# OBD-II-UART.net
KiCad netlist of a schematic drawn in EAGLE
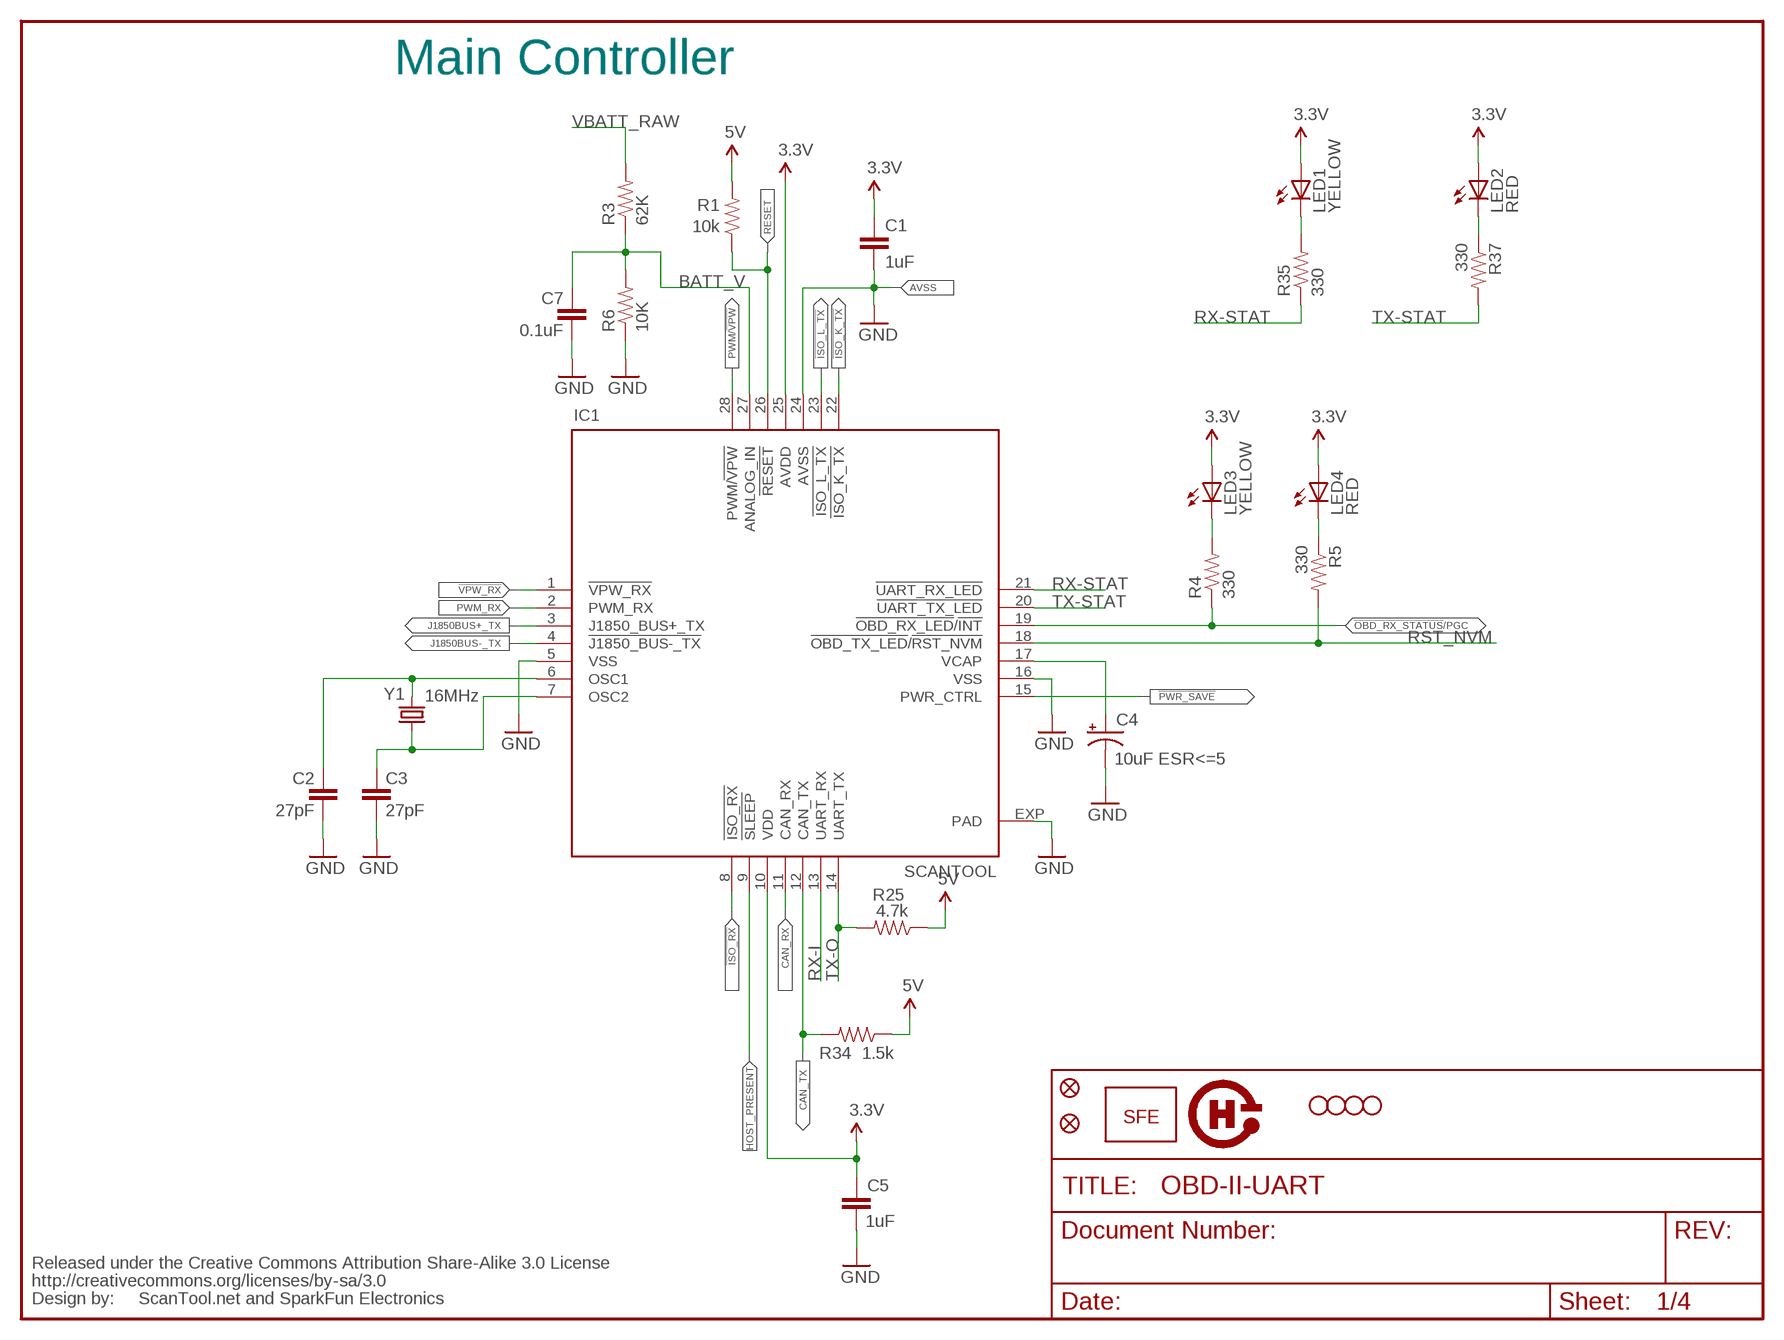
[diagram p0: schematic, sheet 1]
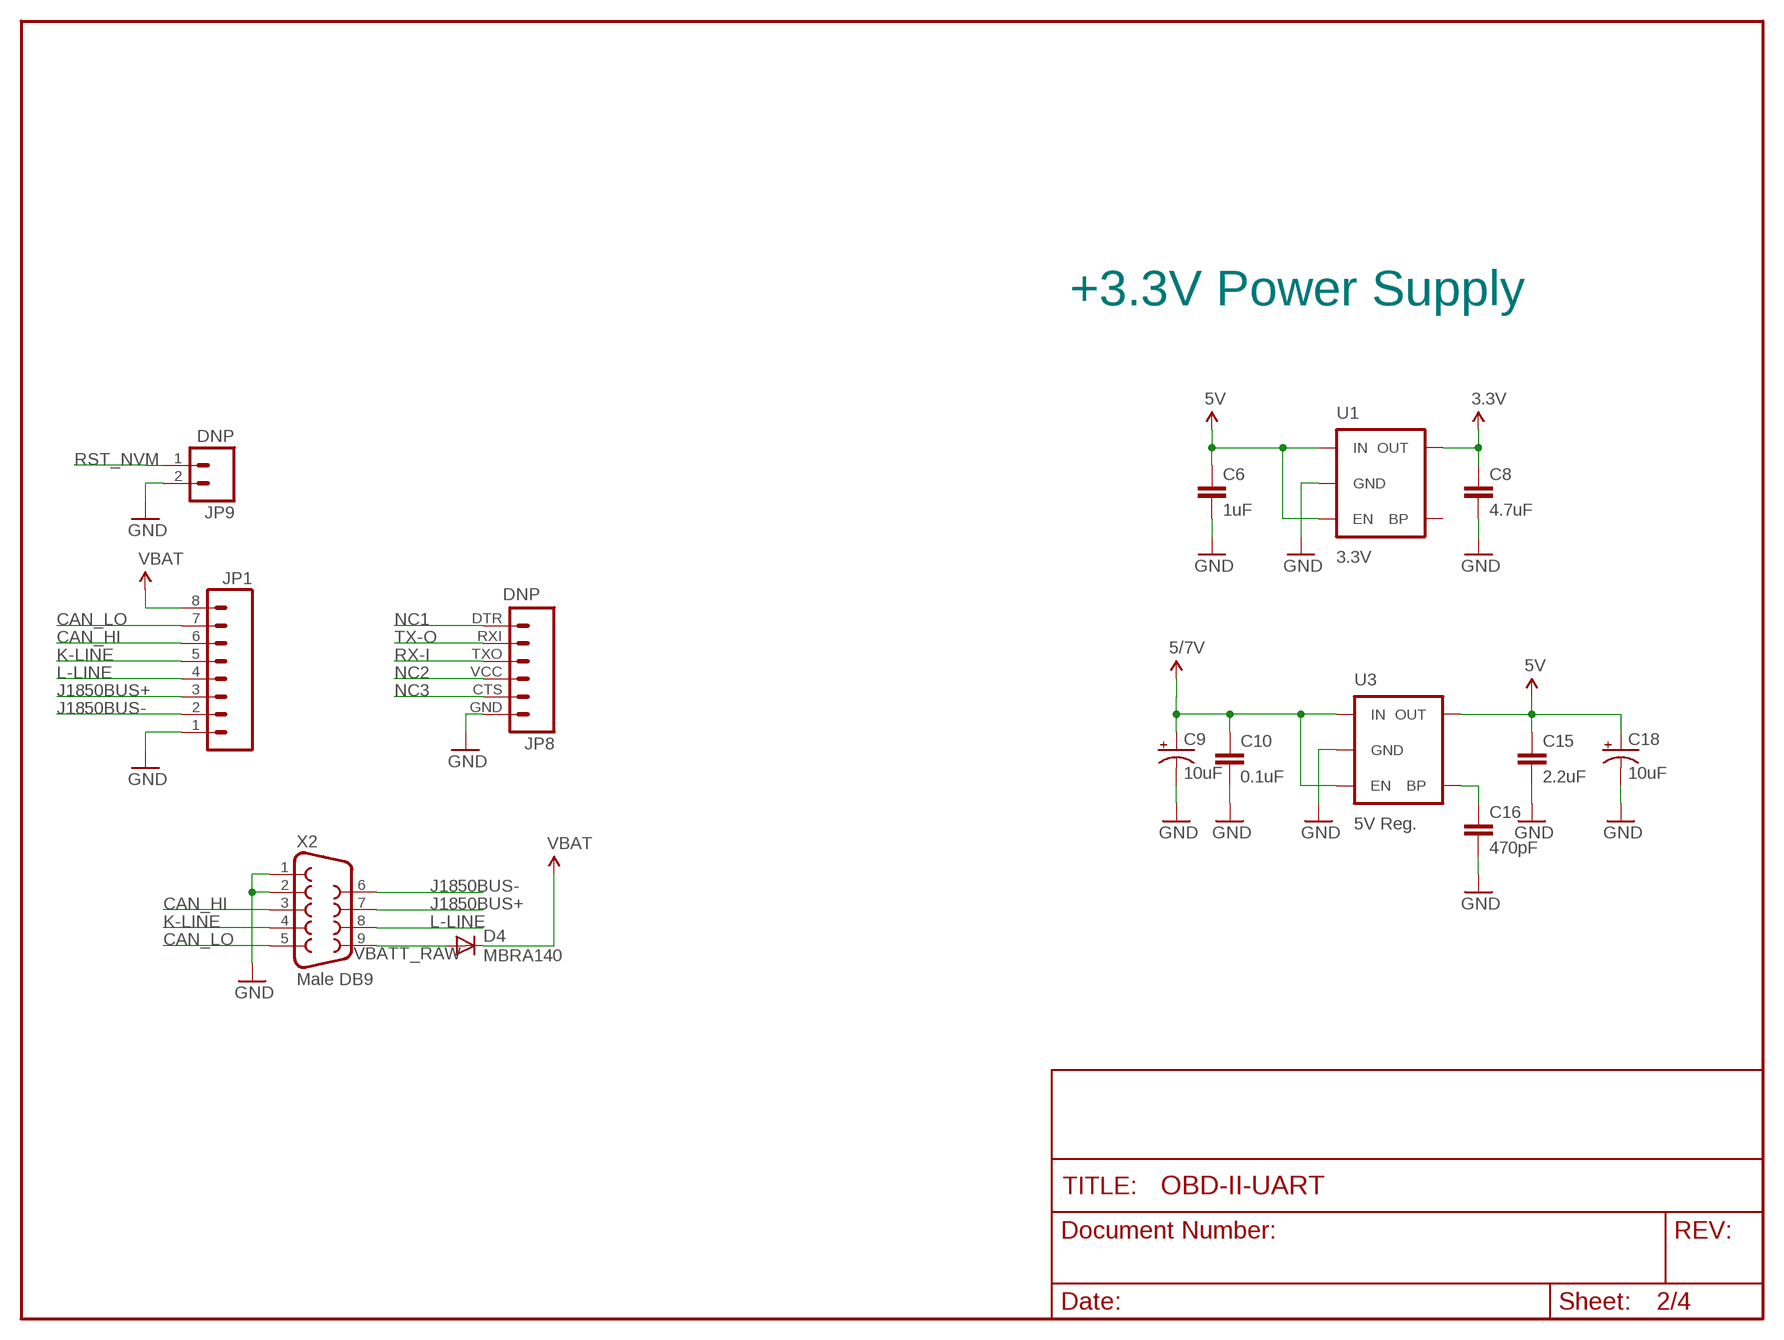
[diagram p1: schematic, sheet 2]
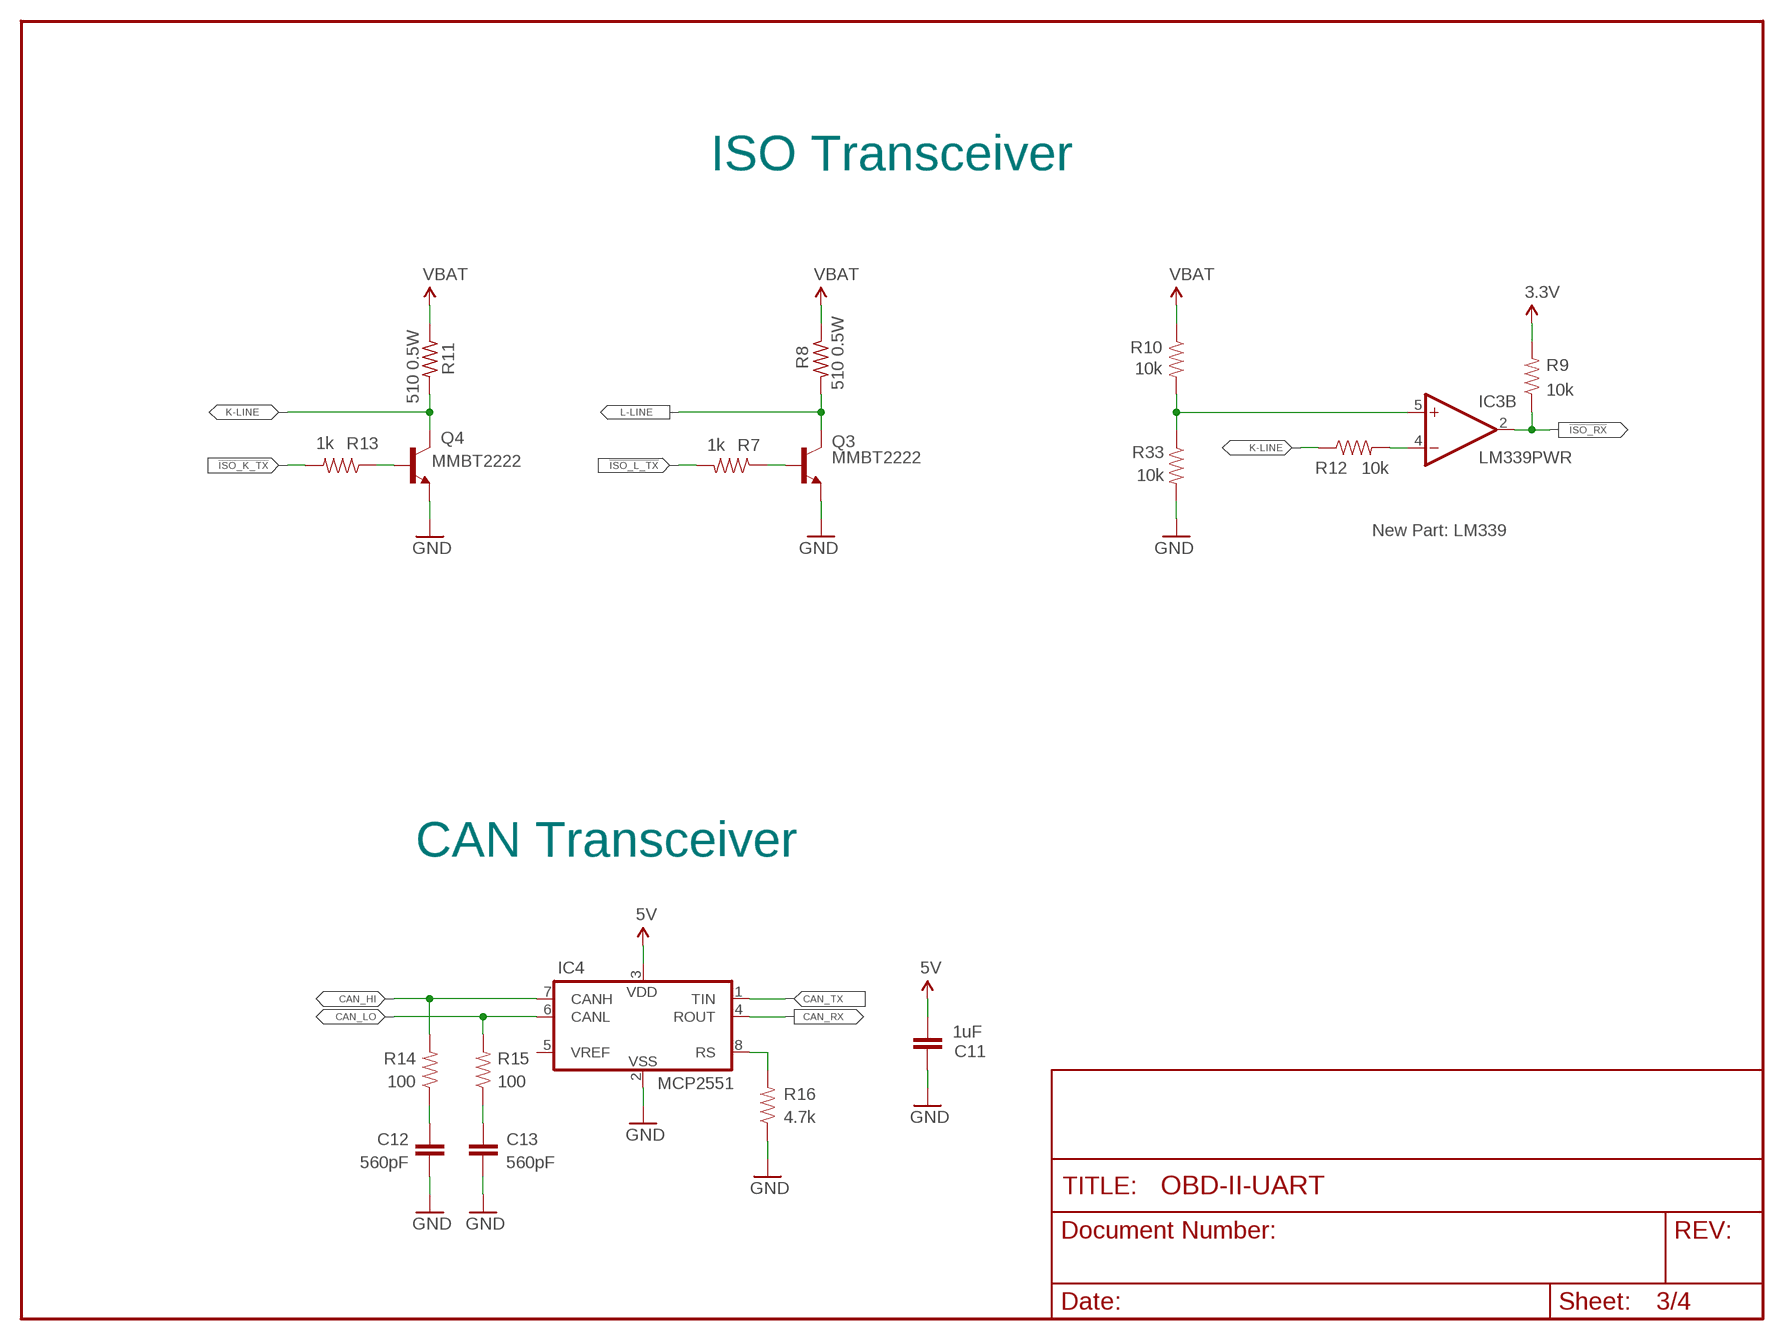
[diagram p2: schematic, sheet 3]
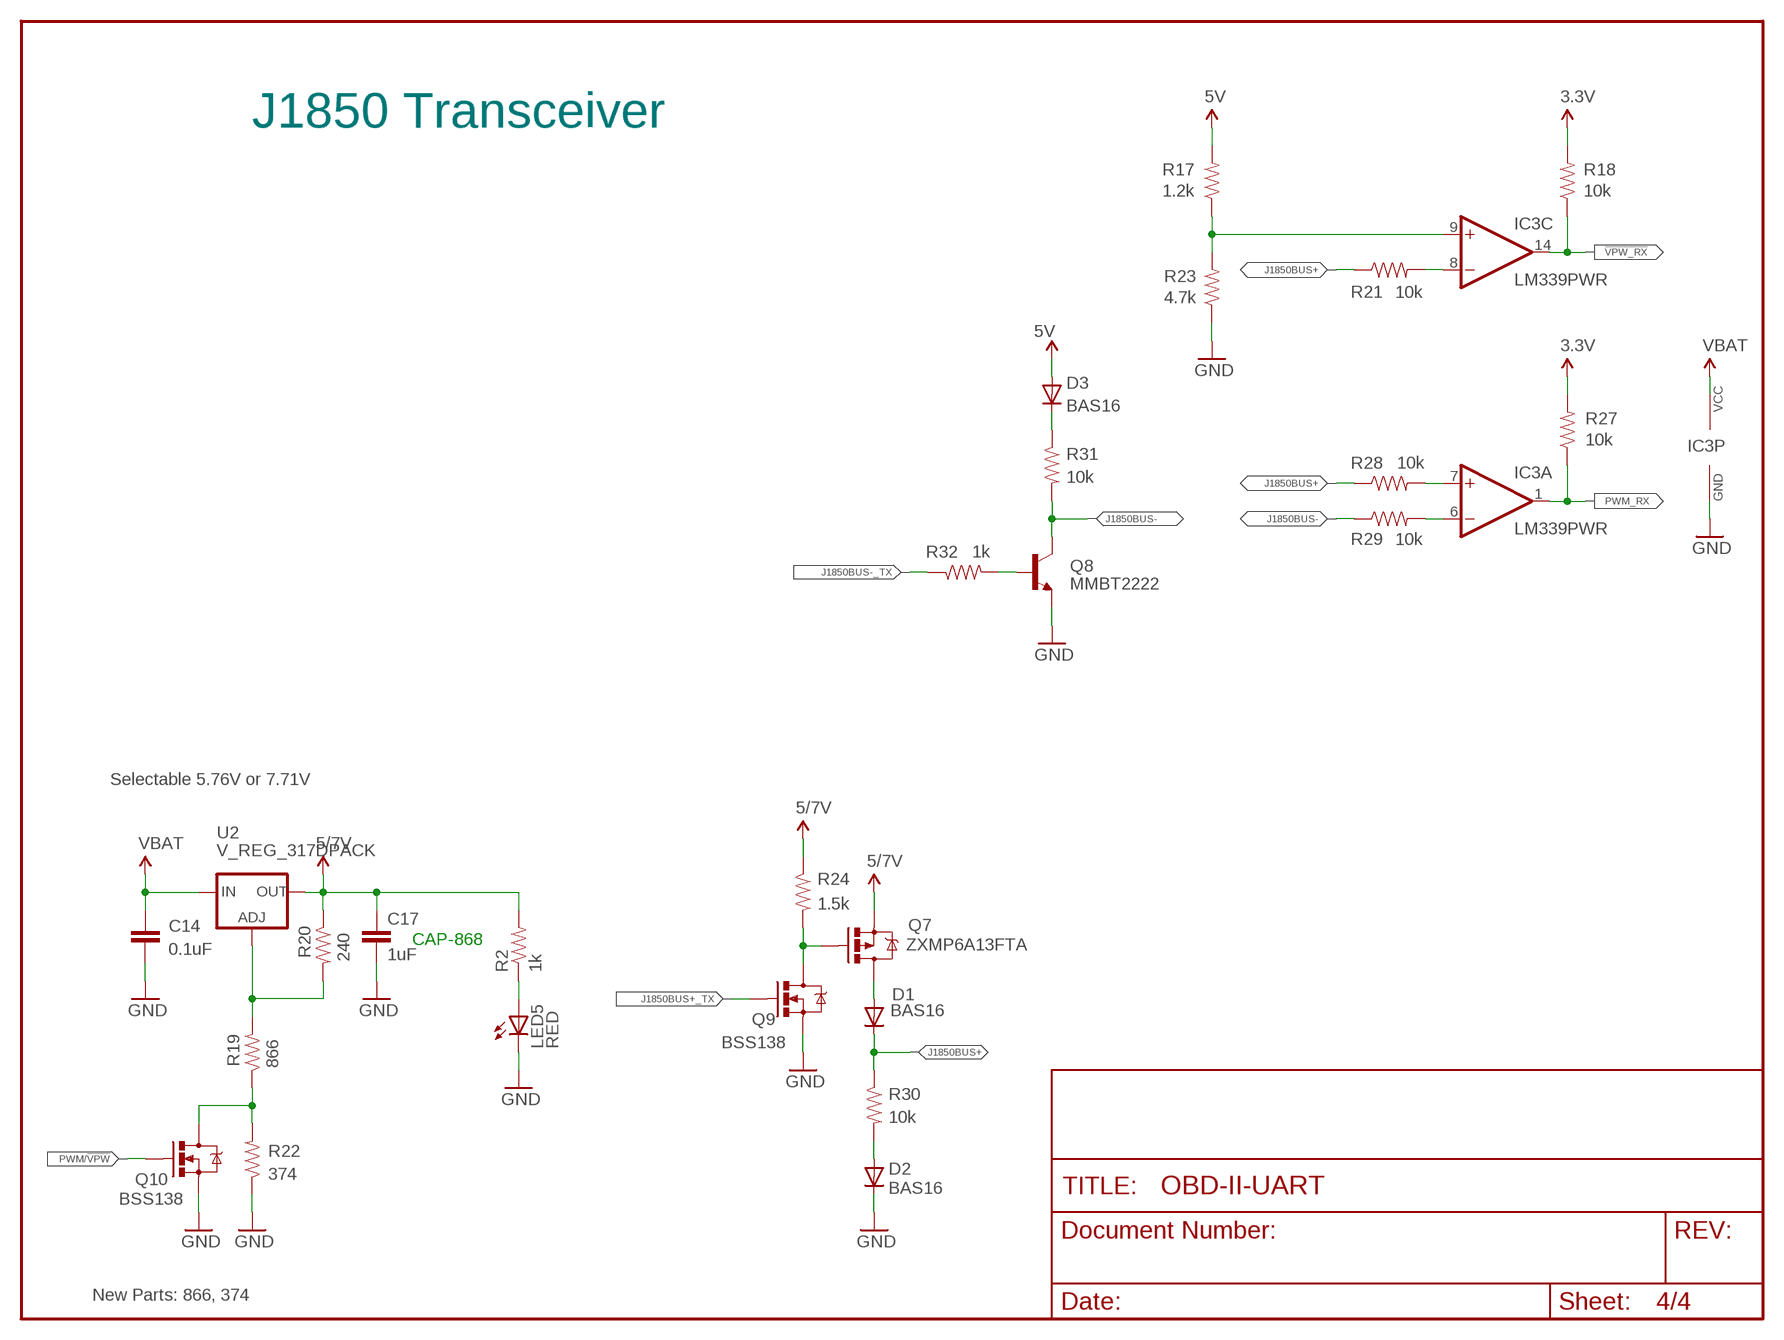
[diagram p3: schematic, sheet 4]

(export (version "E")
  (design (tool "Eeschema 10.0.6"))
  (components
    (comp (ref "C14")
      (value "0.1uF")
      (footprint "eagle-import:0402-CAP")
      (libsource (lib "eagle-import") (part "CAP0402-CAP"))
    )
    (comp (ref "C17")
      (value "1uF")
      (footprint "eagle-import:0402-CAP")
      (libsource (lib "eagle-import") (part "CAP0402-CAP"))
    )
    (comp (ref "D1")
      (value "BAS16")
      (footprint "eagle-import:SOD-323")
      (libsource (lib "eagle-import") (part "DIODESOD"))
    )
    (comp (ref "D2")
      (value "BAS16")
      (footprint "eagle-import:SOD-323")
      (libsource (lib "eagle-import") (part "DIODESOD"))
    )
    (comp (ref "D3")
      (value "BAS16")
      (footprint "eagle-import:SOD-323")
      (libsource (lib "eagle-import") (part "DIODESOD"))
    )
    (comp (ref "IC3")
      (value "LM339PWR")
      (footprint "eagle-import:TSSOP-14")
      (libsource (lib "eagle-import") (part "LM339PWR"))
    )
    (comp (ref "LED5")
      (value "RED")
      (footprint "eagle-import:LED-0603")
      (libsource (lib "eagle-import") (part "LED0603"))
    )
    (comp (ref "Q7")
      (value "ZXMP6A13FTA")
      (footprint "eagle-import:SOT23")
      (libsource (lib "eagle-import") (part "MOSFET-PCHANNEL"))
    )
    (comp (ref "Q8")
      (value "MMBT2222")
      (footprint "eagle-import:SOT23-3")
      (libsource (lib "eagle-import") (part "TRANSISTOR_NPNSOT23-3"))
    )
    (comp (ref "Q9")
      (value "BSS138")
      (footprint "eagle-import:SOT23-3")
      (libsource (lib "eagle-import") (part "MOSFET-NCHANNELSMD"))
    )
    (comp (ref "Q10")
      (value "BSS138")
      (footprint "eagle-import:SOT23-3")
      (libsource (lib "eagle-import") (part "MOSFET-NCHANNELSMD"))
    )
    (comp (ref "R2")
      (value "1k")
      (footprint "eagle-import:0402-RES")
      (libsource (lib "eagle-import") (part "RESISTOR0402-RES"))
    )
    (comp (ref "R17")
      (value "1.2k")
      (footprint "eagle-import:0402-RES")
      (libsource (lib "eagle-import") (part "RESISTOR0402-RES"))
    )
    (comp (ref "R18")
      (value "10k")
      (footprint "eagle-import:0402-RES")
      (libsource (lib "eagle-import") (part "RESISTOR0402-RES"))
    )
    (comp (ref "R19")
      (value "866")
      (footprint "eagle-import:0402-RES")
      (libsource (lib "eagle-import") (part "RESISTOR0402-RES"))
    )
    (comp (ref "R20")
      (value "240")
      (footprint "eagle-import:0402-RES")
      (libsource (lib "eagle-import") (part "RESISTOR0402-RES"))
    )
    (comp (ref "R21")
      (value "10k")
      (footprint "eagle-import:0402-RES")
      (libsource (lib "eagle-import") (part "RESISTOR0402-RES"))
    )
    (comp (ref "R22")
      (value "374")
      (footprint "eagle-import:0402-RES")
      (libsource (lib "eagle-import") (part "RESISTOR0402-RES"))
    )
    (comp (ref "R23")
      (value "4.7k")
      (footprint "eagle-import:0402-RES")
      (libsource (lib "eagle-import") (part "RESISTOR0402-RES"))
    )
    (comp (ref "R24")
      (value "1.5k")
      (footprint "eagle-import:0402-RES")
      (libsource (lib "eagle-import") (part "RESISTOR0402-RES"))
    )
    (comp (ref "R27")
      (value "10k")
      (footprint "eagle-import:0402-RES")
      (libsource (lib "eagle-import") (part "RESISTOR0402-RES"))
    )
    (comp (ref "R28")
      (value "10k")
      (footprint "eagle-import:0402-RES")
      (libsource (lib "eagle-import") (part "RESISTOR0402-RES"))
    )
    (comp (ref "R29")
      (value "10k")
      (footprint "eagle-import:0402-RES")
      (libsource (lib "eagle-import") (part "RESISTOR0402-RES"))
    )
    (comp (ref "R30")
      (value "10k")
      (footprint "eagle-import:0402-RES")
      (libsource (lib "eagle-import") (part "RESISTOR0402-RES"))
    )
    (comp (ref "R31")
      (value "10k")
      (footprint "eagle-import:0402-RES")
      (libsource (lib "eagle-import") (part "RESISTOR0402-RES"))
    )
    (comp (ref "R32")
      (value "1k")
      (footprint "eagle-import:0402-RES")
      (libsource (lib "eagle-import") (part "RESISTOR0402-RES"))
    )
    (comp (ref "U2")
      (value "V_REG_317DPACK")
      (footprint "eagle-import:V-REG_DPACK")
      (libsource (lib "eagle-import") (part "V_REG_317DPACK"))
    )
    (comp (ref "C11")
      (value "1uF")
      (footprint "eagle-import:0402-CAP")
      (libsource (lib "eagle-import") (part "CAP0402-CAP"))
    )
    (comp (ref "C12")
      (value "560pF")
      (footprint "eagle-import:0402-CAP")
      (libsource (lib "eagle-import") (part "CAP0402-CAP"))
    )
    (comp (ref "C13")
      (value "560pF")
      (footprint "eagle-import:0402-CAP")
      (libsource (lib "eagle-import") (part "CAP0402-CAP"))
    )
    (comp (ref "IC4")
      (value "MCP2551")
      (footprint "eagle-import:SO-8")
      (fields (field (name "PARTNUM") "MCP2551-I/SN"))
      (libsource (lib "eagle-import") (part "MCP2551-I/SN"))
    )
    (comp (ref "Q3")
      (value "MMBT2222")
      (footprint "eagle-import:SOT23-3")
      (libsource (lib "eagle-import") (part "TRANSISTOR_NPNSOT23-3"))
    )
    (comp (ref "Q4")
      (value "MMBT2222")
      (footprint "eagle-import:SOT23-3")
      (libsource (lib "eagle-import") (part "TRANSISTOR_NPNSOT23-3"))
    )
    (comp (ref "R7")
      (value "1k")
      (footprint "eagle-import:0402-RES")
      (libsource (lib "eagle-import") (part "RESISTOR0402-RES"))
    )
    (comp (ref "R8")
      (value "510 0.5W")
      (footprint "eagle-import:2010")
      (libsource (lib "eagle-import") (part "R-US_2010"))
    )
    (comp (ref "R9")
      (value "10k")
      (footprint "eagle-import:0402-RES")
      (libsource (lib "eagle-import") (part "RESISTOR0402-RES"))
    )
    (comp (ref "R10")
      (value "10k")
      (footprint "eagle-import:0402-RES")
      (libsource (lib "eagle-import") (part "RESISTOR0402-RES"))
    )
    (comp (ref "R11")
      (value "510 0.5W")
      (footprint "eagle-import:2010")
      (libsource (lib "eagle-import") (part "R-US_2010"))
    )
    (comp (ref "R12")
      (value "10k")
      (footprint "eagle-import:0402-RES")
      (libsource (lib "eagle-import") (part "RESISTOR0402-RES"))
    )
    (comp (ref "R13")
      (value "1k")
      (footprint "eagle-import:0402-RES")
      (libsource (lib "eagle-import") (part "RESISTOR0402-RES"))
    )
    (comp (ref "R14")
      (value "100")
      (footprint "eagle-import:0402-RES")
      (libsource (lib "eagle-import") (part "RESISTOR0402-RES"))
    )
    (comp (ref "R15")
      (value "100")
      (footprint "eagle-import:0402-RES")
      (libsource (lib "eagle-import") (part "RESISTOR0402-RES"))
    )
    (comp (ref "R16")
      (value "4.7k")
      (footprint "eagle-import:0402-RES")
      (libsource (lib "eagle-import") (part "RESISTOR0402-RES"))
    )
    (comp (ref "R33")
      (value "10k")
      (footprint "eagle-import:0402-RES")
      (libsource (lib "eagle-import") (part "RESISTOR0402-RES"))
    )
    (comp (ref "C1")
      (value "1uF")
      (footprint "eagle-import:0402-CAP")
      (libsource (lib "eagle-import") (part "CAP0402-CAP"))
    )
    (comp (ref "C2")
      (value "27pF")
      (footprint "eagle-import:0402-CAP")
      (libsource (lib "eagle-import") (part "CAP0402-CAP"))
    )
    (comp (ref "C3")
      (value "27pF")
      (footprint "eagle-import:0402-CAP")
      (libsource (lib "eagle-import") (part "CAP0402-CAP"))
    )
    (comp (ref "C4")
      (value "10uF ESR<=5")
      (footprint "eagle-import:EIA3216")
      (libsource (lib "eagle-import") (part "CAP_POL1206"))
    )
    (comp (ref "C5")
      (value "1uF")
      (footprint "eagle-import:0402-CAP")
      (libsource (lib "eagle-import") (part "CAP0402-CAP"))
    )
    (comp (ref "C7")
      (value "0.1uF")
      (footprint "eagle-import:0402-CAP")
      (libsource (lib "eagle-import") (part "CAP0402-CAP"))
    )
    (comp (ref "IC1")
      (value "SCANTOOL")
      (footprint "eagle-import:_STN_SCANTOOL_QFN-28-S")
      (libsource (lib "eagle-import") (part "SCANTOOL"))
    )
    (comp (ref "JP2")
      (value "FIDUCIAL1X2")
      (footprint "eagle-import:FIDUCIAL-1X2")
      (libsource (lib "eagle-import") (part "FIDUCIAL1X2"))
    )
    (comp (ref "JP3")
      (value "LOGO-SFENEW")
      (footprint "eagle-import:SFE-NEW-WEBLOGO")
      (libsource (lib "eagle-import") (part "LOGO-SFENEW"))
    )
    (comp (ref "JP4")
      (value "STAND-OFF")
      (footprint "eagle-import:STAND-OFF")
      (libsource (lib "eagle-import") (part "STAND-OFF"))
    )
    (comp (ref "JP5")
      (value "STAND-OFF")
      (footprint "eagle-import:STAND-OFF")
      (libsource (lib "eagle-import") (part "STAND-OFF"))
    )
    (comp (ref "JP6")
      (value "STAND-OFF")
      (footprint "eagle-import:STAND-OFF")
      (libsource (lib "eagle-import") (part "STAND-OFF"))
    )
    (comp (ref "JP7")
      (value "STAND-OFF")
      (footprint "eagle-import:STAND-OFF")
      (libsource (lib "eagle-import") (part "STAND-OFF"))
    )
    (comp (ref "JP10")
      (value "FIDUCIAL1X2")
      (footprint "eagle-import:FIDUCIAL-1X2")
      (libsource (lib "eagle-import") (part "FIDUCIAL1X2"))
    )
    (comp (ref "LED1")
      (value "YELLOW")
      (footprint "eagle-import:LED-0603")
      (libsource (lib "eagle-import") (part "LED0603"))
    )
    (comp (ref "LED2")
      (value "RED")
      (footprint "eagle-import:LED-0603")
      (libsource (lib "eagle-import") (part "LED0603"))
    )
    (comp (ref "LED3")
      (value "YELLOW")
      (footprint "eagle-import:LED-0603")
      (libsource (lib "eagle-import") (part "LED0603"))
    )
    (comp (ref "LED4")
      (value "RED")
      (footprint "eagle-import:LED-0603")
      (libsource (lib "eagle-import") (part "LED0603"))
    )
    (comp (ref "R1")
      (value "10k")
      (footprint "eagle-import:0402-RES")
      (libsource (lib "eagle-import") (part "RESISTOR0402-RES"))
    )
    (comp (ref "R3")
      (value "62K")
      (footprint "eagle-import:0402-RES")
      (libsource (lib "eagle-import") (part "RESISTOR0402-RES"))
    )
    (comp (ref "R4")
      (value "330")
      (footprint "eagle-import:0402-RES")
      (libsource (lib "eagle-import") (part "RESISTOR0402-RES"))
    )
    (comp (ref "R5")
      (value "330")
      (footprint "eagle-import:0402-RES")
      (libsource (lib "eagle-import") (part "RESISTOR0402-RES"))
    )
    (comp (ref "R6")
      (value "10K")
      (footprint "eagle-import:0402-RES")
      (libsource (lib "eagle-import") (part "RESISTOR0402-RES"))
    )
    (comp (ref "R25")
      (value "4.7k")
      (footprint "eagle-import:0402-RES")
      (libsource (lib "eagle-import") (part "RESISTOR0402-RES"))
    )
    (comp (ref "R34")
      (value "1.5k")
      (footprint "eagle-import:0402-RES")
      (libsource (lib "eagle-import") (part "RESISTOR0402-RES"))
    )
    (comp (ref "R35")
      (value "330")
      (footprint "eagle-import:0402-RES")
      (libsource (lib "eagle-import") (part "RESISTOR0402-RES"))
    )
    (comp (ref "R37")
      (value "330")
      (footprint "eagle-import:0402-RES")
      (libsource (lib "eagle-import") (part "RESISTOR0402-RES"))
    )
    (comp (ref "U$1")
      (value "CREATIVE_COMMONS")
      (footprint "eagle-import:CREATIVE_COMMONS")
      (libsource (lib "eagle-import") (part "CREATIVE_COMMONS"))
    )
    (comp (ref "U$14")
      (value "OSHW-LOGO")
      (footprint "eagle-import:OSHW-LOGO")
      (libsource (lib "eagle-import") (part "OSHW-LOGO"))
    )
    (comp (ref "Y1")
      (value "16MHz")
      (footprint "eagle-import:CRYSTAL-SMD-5X3")
      (libsource (lib "eagle-import") (part "CRYSTAL5X3"))
    )
    (comp (ref "C6")
      (value "1uF")
      (footprint "eagle-import:0402-CAP")
      (libsource (lib "eagle-import") (part "CAP0402-CAP"))
    )
    (comp (ref "C8")
      (value "4.7uF")
      (footprint "eagle-import:0402-CAP")
      (libsource (lib "eagle-import") (part "CAP0402-CAP"))
    )
    (comp (ref "C9")
      (value "10uF")
      (footprint "eagle-import:EIA3216")
      (libsource (lib "eagle-import") (part "CAP_POL1206"))
    )
    (comp (ref "C10")
      (value "0.1uF")
      (footprint "eagle-import:0402-CAP")
      (libsource (lib "eagle-import") (part "CAP0402-CAP"))
    )
    (comp (ref "C15")
      (value "2.2uF")
      (footprint "eagle-import:0402-CAP")
      (libsource (lib "eagle-import") (part "CAP0402-CAP"))
    )
    (comp (ref "C16")
      (value "470pF")
      (footprint "eagle-import:0402-CAP")
      (libsource (lib "eagle-import") (part "CAP0402-CAP"))
    )
    (comp (ref "C18")
      (value "10uF")
      (footprint "eagle-import:EIA3216")
      (libsource (lib "eagle-import") (part "CAP_POL1206"))
    )
    (comp (ref "D4")
      (value "MBRA140")
      (footprint "eagle-import:SMA-DIODE")
      (libsource (lib "eagle-import") (part "DIODESMA"))
    )
    (comp (ref "JP1")
      (value "M08")
      (footprint "eagle-import:1X08")
      (libsource (lib "eagle-import") (part "M08"))
    )
    (comp (ref "JP8")
      (value "DNP")
      (footprint "eagle-import:FTDI_BASIC")
      (libsource (lib "eagle-import") (part "FTDI_BASICPTH"))
    )
    (comp (ref "JP9")
      (value "DNP")
      (footprint "eagle-import:1X02")
      (libsource (lib "eagle-import") (part "M02PTH"))
    )
    (comp (ref "U1")
      (value "3.3V")
      (footprint "eagle-import:SOT23-5")
      (libsource (lib "eagle-import") (part "V_REG_LDOSMD"))
    )
    (comp (ref "U3")
      (value "5V Reg.")
      (footprint "eagle-import:SOT23-5")
      (libsource (lib "eagle-import") (part "V_REG_LDOSMD"))
    )
    (comp (ref "X2")
      (value "Male DB9")
      (footprint "eagle-import:DB9_MALE")
      (libsource (lib "eagle-import") (part "DB9MALE"))
    )
  )
  (nets
    (net (code "1") (name "3.3V") (class "Default")
      (node (ref "C1") (pin "1") (pinfunction "1_1") (pintype "passive"))
      (node (ref "C5") (pin "1") (pinfunction "1_1") (pintype "passive"))
      (node (ref "C8") (pin "1") (pinfunction "1_1") (pintype "passive"))
      (node (ref "IC1") (pin "10") (pinfunction "VDD_10") (pintype "power_in"))
      (node (ref "IC1") (pin "25") (pinfunction "AVDD_25") (pintype "power_in"))
      (node (ref "LED1") (pin "A") (pinfunction "A_A") (pintype "passive"))
      (node (ref "LED2") (pin "A") (pinfunction "A_A") (pintype "passive"))
      (node (ref "LED3") (pin "A") (pinfunction "A_A") (pintype "passive"))
      (node (ref "LED4") (pin "A") (pinfunction "A_A") (pintype "passive"))
      (node (ref "R18") (pin "2") (pinfunction "2_2") (pintype "passive"))
      (node (ref "R27") (pin "2") (pinfunction "2_2") (pintype "passive"))
      (node (ref "R9") (pin "2") (pinfunction "2_2") (pintype "passive"))
      (node (ref "U1") (pin "5") (pinfunction "OUT_5") (pintype "passive"))
    )
    (net (code "2") (name "5V") (class "Default")
      (node (ref "C11") (pin "1") (pinfunction "1_1") (pintype "passive"))
      (node (ref "C15") (pin "1") (pinfunction "1_1") (pintype "passive"))
      (node (ref "C18") (pin "A") (pinfunction "+_A") (pintype "passive"))
      (node (ref "C6") (pin "1") (pinfunction "1_1") (pintype "passive"))
      (node (ref "D3") (pin "2") (pinfunction "A_2") (pintype "passive"))
      (node (ref "IC4") (pin "3") (pinfunction "VDD_3") (pintype "power_in"))
      (node (ref "R1") (pin "2") (pinfunction "2_2") (pintype "passive"))
      (node (ref "R17") (pin "2") (pinfunction "2_2") (pintype "passive"))
      (node (ref "R25") (pin "1") (pinfunction "1_1") (pintype "passive"))
      (node (ref "R34") (pin "1") (pinfunction "1_1") (pintype "passive"))
      (node (ref "U1") (pin "1") (pinfunction "IN_1") (pintype "input"))
      (node (ref "U1") (pin "3") (pinfunction "EN_3") (pintype "input"))
      (node (ref "U3") (pin "5") (pinfunction "OUT_5") (pintype "passive"))
    )
    (net (code "3") (name "BATT_V") (class "Default")
      (node (ref "C7") (pin "1") (pinfunction "1_1") (pintype "passive"))
      (node (ref "IC1") (pin "27") (pinfunction "ANALOG_IN_27") (pintype "input"))
      (node (ref "R3") (pin "1") (pinfunction "1_1") (pintype "passive"))
      (node (ref "R6") (pin "2") (pinfunction "2_2") (pintype "passive"))
    )
    (net (code "4") (name "CAN_HI") (class "Default")
      (node (ref "IC4") (pin "7") (pinfunction "CANH_7") (pintype "bidirectional"))
      (node (ref "JP1") (pin "6") (pinfunction "6_6") (pintype "passive"))
      (node (ref "R14") (pin "2") (pinfunction "2_2") (pintype "passive"))
      (node (ref "X2") (pin "3") (pinfunction "3_3") (pintype "passive"))
    )
    (net (code "5") (name "CAN_LO") (class "Default")
      (node (ref "IC4") (pin "6") (pinfunction "CANL_6") (pintype "bidirectional"))
      (node (ref "JP1") (pin "7") (pinfunction "7_7") (pintype "passive"))
      (node (ref "R15") (pin "2") (pinfunction "2_2") (pintype "passive"))
      (node (ref "X2") (pin "5") (pinfunction "5_5") (pintype "passive"))
    )
    (net (code "6") (name "CAN_RX") (class "Default")
      (node (ref "IC1") (pin "11") (pinfunction "CAN_RX_11") (pintype "input"))
      (node (ref "IC4") (pin "4") (pinfunction "ROUT_4") (pintype "output"))
    )
    (net (code "7") (name "CAN_TX") (class "Default")
      (node (ref "IC1") (pin "12") (pinfunction "CAN_TX_12") (pintype "output"))
      (node (ref "IC4") (pin "1") (pinfunction "TIN_1") (pintype "input"))
      (node (ref "R34") (pin "2") (pinfunction "2_2") (pintype "passive"))
    )
    (net (code "8") (name "GND") (class "Default")
      (node (ref "C1") (pin "2") (pinfunction "2_2") (pintype "passive"))
      (node (ref "C10") (pin "2") (pinfunction "2_2") (pintype "passive"))
      (node (ref "C11") (pin "2") (pinfunction "2_2") (pintype "passive"))
      (node (ref "C12") (pin "2") (pinfunction "2_2") (pintype "passive"))
      (node (ref "C13") (pin "2") (pinfunction "2_2") (pintype "passive"))
      (node (ref "C14") (pin "2") (pinfunction "2_2") (pintype "passive"))
      (node (ref "C15") (pin "2") (pinfunction "2_2") (pintype "passive"))
      (node (ref "C16") (pin "2") (pinfunction "2_2") (pintype "passive"))
      (node (ref "C17") (pin "2") (pinfunction "2_2") (pintype "passive"))
      (node (ref "C18") (pin "C") (pinfunction "-_C") (pintype "passive"))
      (node (ref "C2") (pin "2") (pinfunction "2_2") (pintype "passive"))
      (node (ref "C3") (pin "2") (pinfunction "2_2") (pintype "passive"))
      (node (ref "C4") (pin "C") (pinfunction "-_C") (pintype "passive"))
      (node (ref "C5") (pin "2") (pinfunction "2_2") (pintype "passive"))
      (node (ref "C6") (pin "2") (pinfunction "2_2") (pintype "passive"))
      (node (ref "C7") (pin "2") (pinfunction "2_2") (pintype "passive"))
      (node (ref "C8") (pin "2") (pinfunction "2_2") (pintype "passive"))
      (node (ref "C9") (pin "C") (pinfunction "-_C") (pintype "passive"))
      (node (ref "D2") (pin "1") (pinfunction "C_1") (pintype "passive"))
      (node (ref "IC1") (pin "16") (pinfunction "VSS_16") (pintype "power_in"))
      (node (ref "IC1") (pin "24") (pinfunction "AVSS_24") (pintype "power_in"))
      (node (ref "IC1") (pin "5") (pinfunction "VSS_5") (pintype "power_in"))
      (node (ref "IC1") (pin "EXP") (pinfunction "PAD_EXP") (pintype "passive"))
      (node (ref "IC3") (pin "12") (pinfunction "GND_12") (pintype "power_in"))
      (node (ref "IC4") (pin "2") (pinfunction "VSS_2") (pintype "power_in"))
      (node (ref "JP1") (pin "1") (pinfunction "1_1") (pintype "passive"))
      (node (ref "JP8") (pin "GND") (pinfunction "6_GND") (pintype "passive"))
      (node (ref "JP9") (pin "2") (pinfunction "2_2") (pintype "passive"))
      (node (ref "LED5") (pin "C") (pinfunction "C_C") (pintype "passive"))
      (node (ref "Q10") (pin "2") (pinfunction "S_2") (pintype "passive"))
      (node (ref "Q3") (pin "2") (pinfunction "E_2") (pintype "passive"))
      (node (ref "Q4") (pin "2") (pinfunction "E_2") (pintype "passive"))
      (node (ref "Q8") (pin "2") (pinfunction "E_2") (pintype "passive"))
      (node (ref "Q9") (pin "2") (pinfunction "S_2") (pintype "passive"))
      (node (ref "R16") (pin "1") (pinfunction "1_1") (pintype "passive"))
      (node (ref "R22") (pin "1") (pinfunction "1_1") (pintype "passive"))
      (node (ref "R23") (pin "1") (pinfunction "1_1") (pintype "passive"))
      (node (ref "R33") (pin "2") (pinfunction "2_2") (pintype "passive"))
      (node (ref "R6") (pin "1") (pinfunction "1_1") (pintype "passive"))
      (node (ref "U1") (pin "2") (pinfunction "GND_2") (pintype "input"))
      (node (ref "U3") (pin "2") (pinfunction "GND_2") (pintype "input"))
      (node (ref "X2") (pin "1") (pinfunction "1_1") (pintype "passive"))
      (node (ref "X2") (pin "2") (pinfunction "2_2") (pintype "passive"))
    )
    (net (code "9") (name "HOST_PRESENT") (class "Default")
      (node (ref "IC1") (pin "9") (pinfunction "~{SLEEP}_9") (pintype "input"))
    )
    (net (code "10") (name "J1850BUS+") (class "Default")
      (node (ref "D1") (pin "1") (pinfunction "C_1") (pintype "passive"))
      (node (ref "JP1") (pin "3") (pinfunction "3_3") (pintype "passive"))
      (node (ref "R21") (pin "1") (pinfunction "1_1") (pintype "passive"))
      (node (ref "R28") (pin "1") (pinfunction "1_1") (pintype "passive"))
      (node (ref "R30") (pin "1") (pinfunction "1_1") (pintype "passive"))
      (node (ref "X2") (pin "7") (pinfunction "7_7") (pintype "passive"))
    )
    (net (code "11") (name "J1850BUS+_TX") (class "Default")
      (node (ref "IC1") (pin "3") (pinfunction "J1850_BUS+_TX_3") (pintype "output"))
      (node (ref "Q9") (pin "1") (pinfunction "G_1") (pintype "passive"))
    )
    (net (code "12") (name "J1850BUS-") (class "Default")
      (node (ref "JP1") (pin "2") (pinfunction "2_2") (pintype "passive"))
      (node (ref "Q8") (pin "3") (pinfunction "C_3") (pintype "passive"))
      (node (ref "R29") (pin "1") (pinfunction "1_1") (pintype "passive"))
      (node (ref "R31") (pin "2") (pinfunction "2_2") (pintype "passive"))
      (node (ref "X2") (pin "6") (pinfunction "6_6") (pintype "passive"))
    )
    (net (code "13") (name "J1850BUS-_TX") (class "Default")
      (node (ref "IC1") (pin "4") (pinfunction "~{J1850_BUS-_TX}_4") (pintype "output"))
      (node (ref "R32") (pin "1") (pinfunction "1_1") (pintype "passive"))
    )
    (net (code "14") (name "K-LINE") (class "Default")
      (node (ref "JP1") (pin "5") (pinfunction "5_5") (pintype "passive"))
      (node (ref "Q4") (pin "3") (pinfunction "C_3") (pintype "passive"))
      (node (ref "R11") (pin "2") (pinfunction "2_2") (pintype "passive"))
      (node (ref "R12") (pin "1") (pinfunction "1_1") (pintype "passive"))
      (node (ref "X2") (pin "4") (pinfunction "4_4") (pintype "passive"))
    )
    (net (code "15") (name "L-LINE") (class "Default")
      (node (ref "JP1") (pin "4") (pinfunction "4_4") (pintype "passive"))
      (node (ref "Q3") (pin "3") (pinfunction "C_3") (pintype "passive"))
      (node (ref "R8") (pin "2") (pinfunction "2_2") (pintype "passive"))
      (node (ref "X2") (pin "8") (pinfunction "8_8") (pintype "passive"))
    )
    (net (code "16") (name "NC1") (class "Default")
      (node (ref "JP8") (pin "DTR") (pinfunction "1_DTR") (pintype "passive"))
    )
    (net (code "17") (name "NC2") (class "Default")
      (node (ref "JP8") (pin "VCC") (pinfunction "4_VCC") (pintype "passive"))
    )
    (net (code "18") (name "NC3") (class "Default")
      (node (ref "JP8") (pin "CTS") (pinfunction "5_CTS") (pintype "passive"))
    )
    (net (code "19") (name "Net-(C4-+)") (class "Default")
      (node (ref "C4") (pin "A") (pinfunction "+_A") (pintype "passive"))
      (node (ref "IC1") (pin "17") (pinfunction "VCAP_17") (pintype "power_in"))
    )
    (net (code "20") (name "Net-(C12-Pad1)") (class "Default")
      (node (ref "C12") (pin "1") (pinfunction "1_1") (pintype "passive"))
      (node (ref "R14") (pin "1") (pinfunction "1_1") (pintype "passive"))
    )
    (net (code "21") (name "Net-(C13-Pad1)") (class "Default")
      (node (ref "C13") (pin "1") (pinfunction "1_1") (pintype "passive"))
      (node (ref "R15") (pin "1") (pinfunction "1_1") (pintype "passive"))
    )
    (net (code "22") (name "Net-(D1-A)") (class "Default")
      (node (ref "D1") (pin "2") (pinfunction "A_2") (pintype "passive"))
      (node (ref "Q7") (pin "3") (pinfunction "D_3") (pintype "passive"))
    )
    (net (code "23") (name "Net-(D2-A)") (class "Default")
      (node (ref "D2") (pin "2") (pinfunction "A_2") (pintype "passive"))
      (node (ref "R30") (pin "2") (pinfunction "2_2") (pintype "passive"))
    )
    (net (code "24") (name "Net-(D3-C)") (class "Default")
      (node (ref "D3") (pin "1") (pinfunction "C_1") (pintype "passive"))
      (node (ref "R31") (pin "1") (pinfunction "1_1") (pintype "passive"))
    )
    (net (code "25") (name "Net-(IC1-OSC1)") (class "Default")
      (node (ref "C2") (pin "1") (pinfunction "1_1") (pintype "passive"))
      (node (ref "IC1") (pin "6") (pinfunction "OSC1_6") (pintype "input"))
      (node (ref "Y1") (pin "3") (pinfunction "2_3") (pintype "passive"))
    )
    (net (code "26") (name "Net-(IC1-OSC2)") (class "Default")
      (node (ref "C3") (pin "1") (pinfunction "1_1") (pintype "passive"))
      (node (ref "IC1") (pin "7") (pinfunction "OSC2_7") (pintype "output"))
      (node (ref "Y1") (pin "1") (pinfunction "1_1") (pintype "passive"))
    )
    (net (code "27") (name "Net-(IC3A-+IN)") (class "Default")
      (node (ref "IC3") (pin "7") (pinfunction "+IN_7") (pintype "input"))
      (node (ref "R28") (pin "2") (pinfunction "2_2") (pintype "passive"))
    )
    (net (code "28") (name "Net-(IC3A--IN)") (class "Default")
      (node (ref "IC3") (pin "6") (pinfunction "-IN_6") (pintype "input"))
      (node (ref "R29") (pin "2") (pinfunction "2_2") (pintype "passive"))
    )
    (net (code "29") (name "Net-(IC3B-+IN)") (class "Default")
      (node (ref "IC3") (pin "5") (pinfunction "+IN_5") (pintype "input"))
      (node (ref "R10") (pin "2") (pinfunction "2_2") (pintype "passive"))
      (node (ref "R33") (pin "1") (pinfunction "1_1") (pintype "passive"))
    )
    (net (code "30") (name "Net-(IC3B--IN)") (class "Default")
      (node (ref "IC3") (pin "4") (pinfunction "-IN_4") (pintype "input"))
      (node (ref "R12") (pin "2") (pinfunction "2_2") (pintype "passive"))
    )
    (net (code "31") (name "Net-(IC3C-+IN)") (class "Default")
      (node (ref "IC3") (pin "9") (pinfunction "+IN_9") (pintype "input"))
      (node (ref "R17") (pin "1") (pinfunction "1_1") (pintype "passive"))
      (node (ref "R23") (pin "2") (pinfunction "2_2") (pintype "passive"))
    )
    (net (code "32") (name "Net-(IC3C--IN)") (class "Default")
      (node (ref "IC3") (pin "8") (pinfunction "-IN_8") (pintype "input"))
      (node (ref "R21") (pin "2") (pinfunction "2_2") (pintype "passive"))
    )
    (net (code "33") (name "Net-(IC4-RS)") (class "Default")
      (node (ref "IC4") (pin "8") (pinfunction "RS_8") (pintype "input"))
      (node (ref "R16") (pin "2") (pinfunction "2_2") (pintype "passive"))
    )
    (net (code "34") (name "Net-(LED1-PadC)") (class "Default")
      (node (ref "LED1") (pin "C") (pinfunction "C_C") (pintype "passive"))
      (node (ref "R35") (pin "2") (pinfunction "2_2") (pintype "passive"))
    )
    (net (code "35") (name "Net-(LED2-PadC)") (class "Default")
      (node (ref "LED2") (pin "C") (pinfunction "C_C") (pintype "passive"))
      (node (ref "R37") (pin "1") (pinfunction "1_1") (pintype "passive"))
    )
    (net (code "36") (name "Net-(LED3-PadC)") (class "Default")
      (node (ref "LED3") (pin "C") (pinfunction "C_C") (pintype "passive"))
      (node (ref "R4") (pin "2") (pinfunction "2_2") (pintype "passive"))
    )
    (net (code "37") (name "Net-(LED4-PadC)") (class "Default")
      (node (ref "LED4") (pin "C") (pinfunction "C_C") (pintype "passive"))
      (node (ref "R5") (pin "1") (pinfunction "1_1") (pintype "passive"))
    )
    (net (code "38") (name "Net-(LED5-PadA)") (class "Default")
      (node (ref "LED5") (pin "A") (pinfunction "A_A") (pintype "passive"))
      (node (ref "R2") (pin "1") (pinfunction "1_1") (pintype "passive"))
    )
    (net (code "39") (name "Net-(Q3-B)") (class "Default")
      (node (ref "Q3") (pin "1") (pinfunction "B_1") (pintype "passive"))
      (node (ref "R7") (pin "1") (pinfunction "1_1") (pintype "passive"))
    )
    (net (code "40") (name "Net-(Q4-B)") (class "Default")
      (node (ref "Q4") (pin "1") (pinfunction "B_1") (pintype "passive"))
      (node (ref "R13") (pin "1") (pinfunction "1_1") (pintype "passive"))
    )
    (net (code "41") (name "Net-(Q7-G)") (class "Default")
      (node (ref "Q7") (pin "1") (pinfunction "G_1") (pintype "passive"))
      (node (ref "Q9") (pin "3") (pinfunction "D_3") (pintype "passive"))
      (node (ref "R24") (pin "2") (pinfunction "2_2") (pintype "passive"))
    )
    (net (code "42") (name "Net-(Q8-B)") (class "Default")
      (node (ref "Q8") (pin "1") (pinfunction "B_1") (pintype "passive"))
      (node (ref "R32") (pin "2") (pinfunction "2_2") (pintype "passive"))
    )
    (net (code "43") (name "Net-(Q10-D)") (class "Default")
      (node (ref "Q10") (pin "3") (pinfunction "D_3") (pintype "passive"))
      (node (ref "R19") (pin "1") (pinfunction "1_1") (pintype "passive"))
      (node (ref "R22") (pin "2") (pinfunction "2_2") (pintype "passive"))
    )
    (net (code "44") (name "Net-(U2-ADJ)") (class "Default")
      (node (ref "R19") (pin "2") (pinfunction "2_2") (pintype "passive"))
      (node (ref "R20") (pin "2") (pinfunction "2_2") (pintype "passive"))
      (node (ref "U2") (pin "1") (pinfunction "ADJ_1") (pintype "input"))
    )
    (net (code "45") (name "Net-(U3-BP)") (class "Default")
      (node (ref "C16") (pin "1") (pinfunction "1_1") (pintype "passive"))
      (node (ref "U3") (pin "4") (pinfunction "BP_4") (pintype "input"))
    )
    (net (code "46") (name "PWM_RX") (class "Default")
      (node (ref "IC1") (pin "2") (pinfunction "PWM_RX_2") (pintype "input"))
      (node (ref "IC3") (pin "1") (pinfunction "OUT_1") (pintype "output"))
      (node (ref "R27") (pin "1") (pinfunction "1_1") (pintype "passive"))
    )
    (net (code "47") (name "PWM{slash}~{VPW}") (class "Default")
      (node (ref "IC1") (pin "28") (pinfunction "PWM/~{VPW}_28") (pintype "output"))
      (node (ref "Q10") (pin "1") (pinfunction "G_1") (pintype "passive"))
    )
    (net (code "48") (name "RESET") (class "Default")
      (node (ref "IC1") (pin "26") (pinfunction "~{RESET}_26") (pintype "input"))
      (node (ref "R1") (pin "1") (pinfunction "1_1") (pintype "passive"))
    )
    (net (code "49") (name "RST_NVM") (class "Default")
      (node (ref "IC1") (pin "18") (pinfunction "~{OBD_TX_LED}/~{RST_NVM}_18") (pintype "bidirectional"))
      (node (ref "JP9") (pin "1") (pinfunction "1_1") (pintype "passive"))
      (node (ref "R5") (pin "2") (pinfunction "2_2") (pintype "passive"))
    )
    (net (code "50") (name "RX-I") (class "Default")
      (node (ref "IC1") (pin "13") (pinfunction "UART_RX_13") (pintype "input"))
      (node (ref "JP8") (pin "TXO") (pinfunction "3_TXO") (pintype "passive"))
    )
    (net (code "51") (name "RX-STAT") (class "Default")
      (node (ref "IC1") (pin "21") (pinfunction "~{UART_RX_LED}_21") (pintype "output"))
      (node (ref "R35") (pin "1") (pinfunction "1_1") (pintype "passive"))
    )
    (net (code "52") (name "TX-O") (class "Default")
      (node (ref "IC1") (pin "14") (pinfunction "UART_TX_14") (pintype "output"))
      (node (ref "JP8") (pin "RXI") (pinfunction "2_RXI") (pintype "passive"))
      (node (ref "R25") (pin "2") (pinfunction "2_2") (pintype "passive"))
    )
    (net (code "53") (name "TX-STAT") (class "Default")
      (node (ref "IC1") (pin "20") (pinfunction "~{UART_TX_LED}_20") (pintype "output"))
      (node (ref "R37") (pin "2") (pinfunction "2_2") (pintype "passive"))
    )
    (net (code "54") (name "VBAT") (class "Default")
      (node (ref "C14") (pin "1") (pinfunction "1_1") (pintype "passive"))
      (node (ref "D4") (pin "C") (pinfunction "C_C") (pintype "passive"))
      (node (ref "IC3") (pin "3") (pinfunction "VCC_3") (pintype "power_in"))
      (node (ref "JP1") (pin "8") (pinfunction "8_8") (pintype "passive"))
      (node (ref "R10") (pin "1") (pinfunction "1_1") (pintype "passive"))
      (node (ref "R11") (pin "1") (pinfunction "1_1") (pintype "passive"))
      (node (ref "R8") (pin "1") (pinfunction "1_1") (pintype "passive"))
      (node (ref "U2") (pin "3") (pinfunction "IN_3") (pintype "input"))
    )
    (net (code "55") (name "VBATT_RAW") (class "Default")
      (node (ref "D4") (pin "A") (pinfunction "A_A") (pintype "passive"))
      (node (ref "R3") (pin "2") (pinfunction "2_2") (pintype "passive"))
      (node (ref "X2") (pin "9") (pinfunction "9_9") (pintype "passive"))
    )
    (net (code "56") (name "VCC") (class "Default")
      (node (ref "C10") (pin "1") (pinfunction "1_1") (pintype "passive"))
      (node (ref "C17") (pin "1") (pinfunction "1_1") (pintype "passive"))
      (node (ref "C9") (pin "A") (pinfunction "+_A") (pintype "passive"))
      (node (ref "Q7") (pin "2") (pinfunction "S_2") (pintype "passive"))
      (node (ref "R2") (pin "2") (pinfunction "2_2") (pintype "passive"))
      (node (ref "R20") (pin "1") (pinfunction "1_1") (pintype "passive"))
      (node (ref "R24") (pin "1") (pinfunction "1_1") (pintype "passive"))
      (node (ref "U2") (pin "4") (pinfunction "OUT_4") (pintype "output"))
      (node (ref "U3") (pin "1") (pinfunction "IN_1") (pintype "input"))
      (node (ref "U3") (pin "3") (pinfunction "EN_3") (pintype "input"))
    )
    (net (code "57") (name "unconnected-(IC4-VREF-Pad5)") (class "Default")
      (node (ref "IC4") (pin "5") (pinfunction "VREF_5") (pintype "output"))
    )
    (net (code "58") (name "unconnected-(U1-BP-Pad4)") (class "Default")
      (node (ref "U1") (pin "4") (pinfunction "BP_4") (pintype "input"))
    )
    (net (code "59") (name "~{ISO_K_TX}") (class "Default")
      (node (ref "IC1") (pin "22") (pinfunction "~{ISO_K_TX}_22") (pintype "output"))
      (node (ref "R13") (pin "2") (pinfunction "2_2") (pintype "passive"))
    )
    (net (code "60") (name "~{ISO_L_TX}") (class "Default")
      (node (ref "IC1") (pin "23") (pinfunction "~{ISO_L_TX}_23") (pintype "output"))
      (node (ref "R7") (pin "2") (pinfunction "2_2") (pintype "passive"))
    )
    (net (code "61") (name "~{ISO_RX}") (class "Default")
      (node (ref "IC1") (pin "8") (pinfunction "~{ISO_RX}_8") (pintype "input"))
      (node (ref "IC3") (pin "2") (pinfunction "OUT_2") (pintype "output"))
      (node (ref "R9") (pin "1") (pinfunction "1_1") (pintype "passive"))
    )
    (net (code "62") (name "~{OBD_RX_STATUS}{slash}PGC") (class "Default")
      (node (ref "IC1") (pin "19") (pinfunction "~{OBD_RX_LED}/~{INT}_19") (pintype "output"))
      (node (ref "R4") (pin "1") (pinfunction "1_1") (pintype "passive"))
    )
    (net (code "63") (name "~{PWR_SAVE}") (class "Default")
      (node (ref "IC1") (pin "15") (pinfunction "PWR_CTRL_15") (pintype "output"))
    )
    (net (code "64") (name "~{VPW_RX}") (class "Default")
      (node (ref "IC1") (pin "1") (pinfunction "~{VPW_RX}_1") (pintype "input"))
      (node (ref "IC3") (pin "14") (pinfunction "OUT_14") (pintype "output"))
      (node (ref "R18") (pin "1") (pinfunction "1_1") (pintype "passive"))
    )
  )
)
